# RAMPSXB.net
KiCad netlist of a schematic drawn in EAGLE
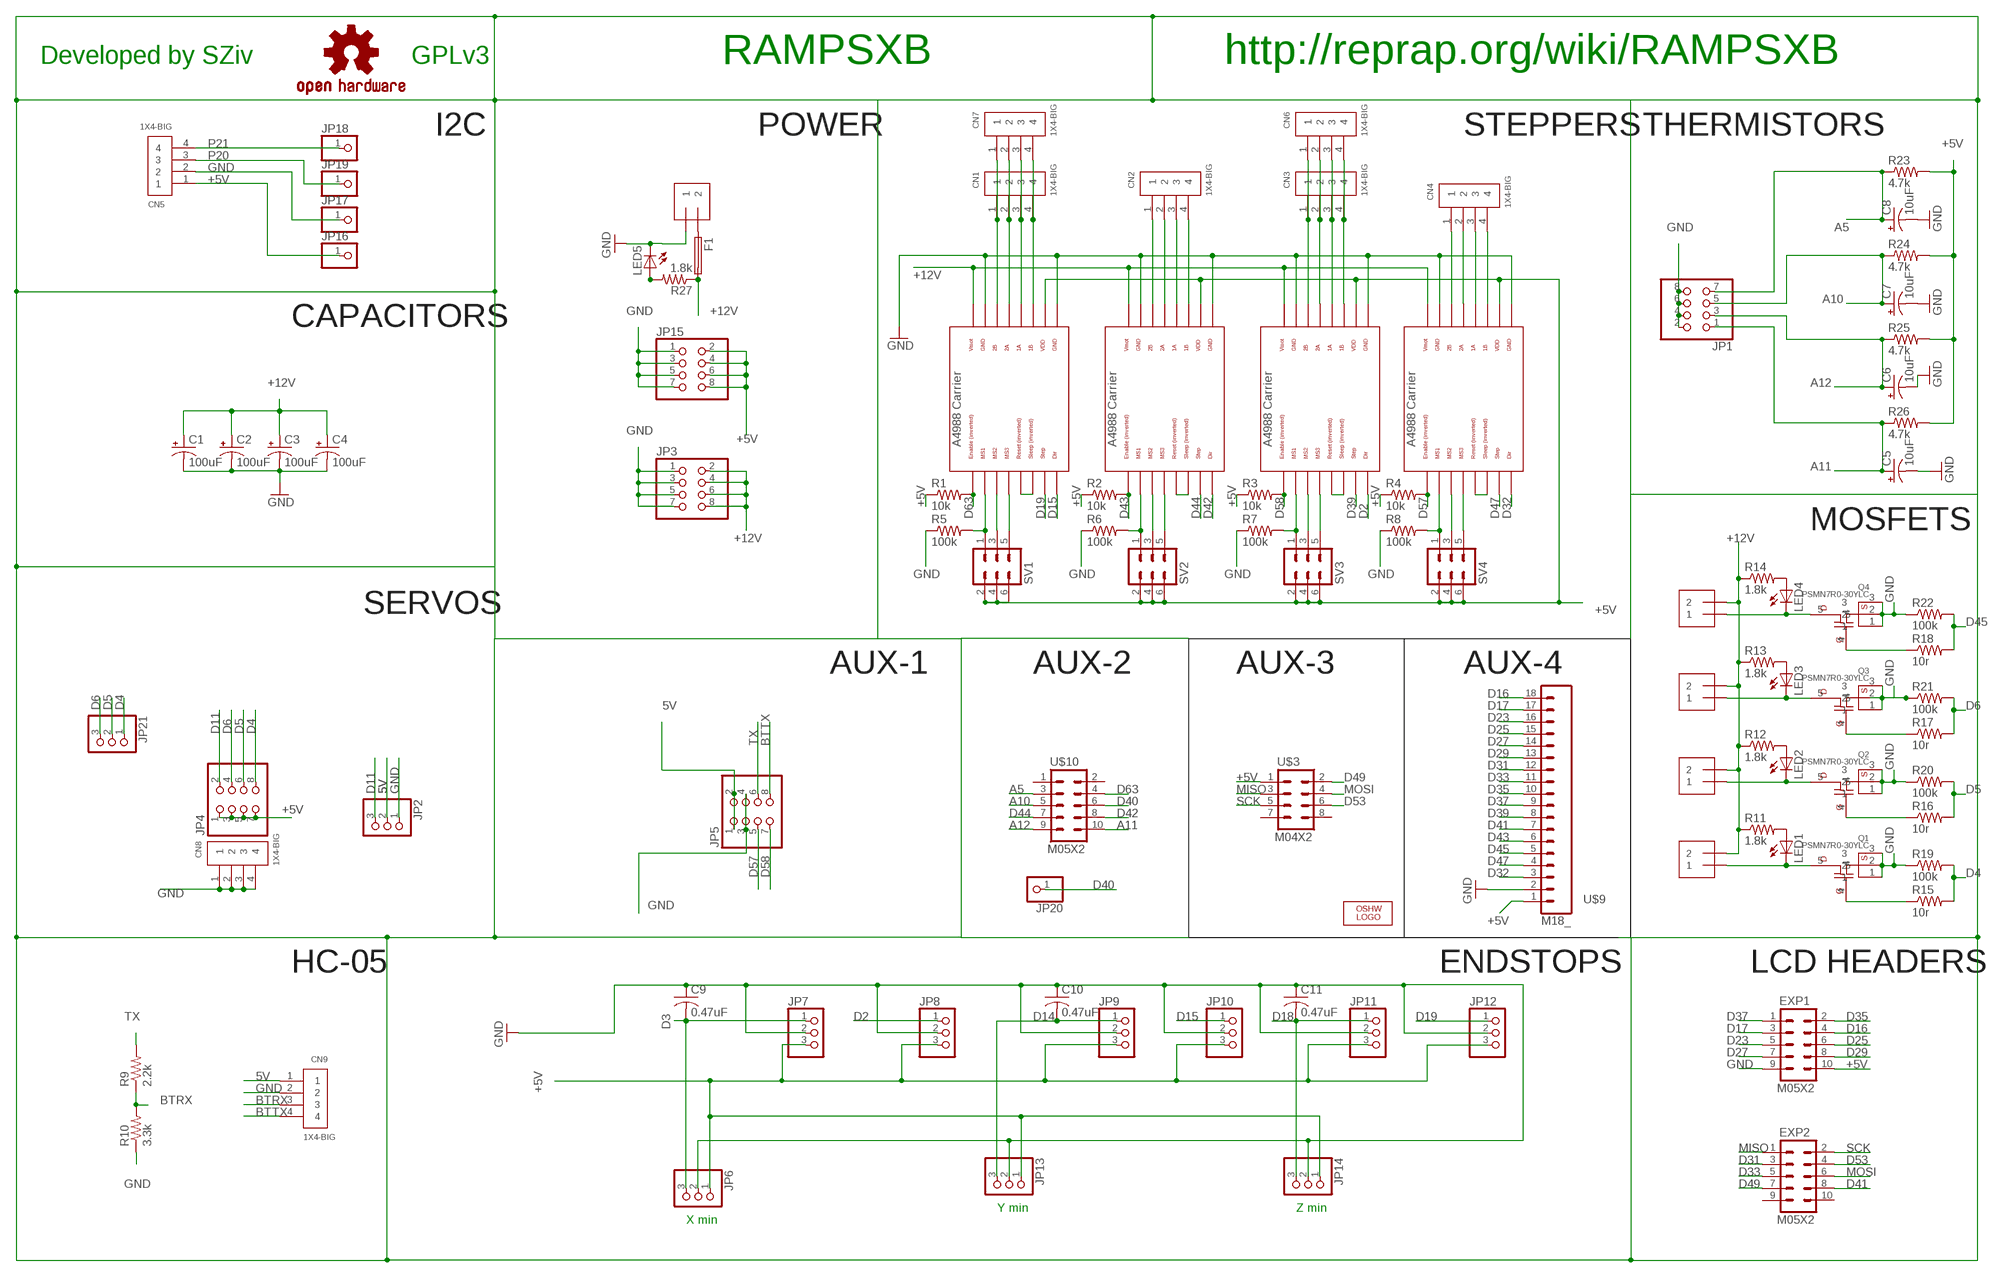
[diagram p0: schematic, sheet 1]

(export (version "E")
  (design (tool "Eeschema 10.0.6"))
  (components
    (comp (ref "C1")
      (value "100uF")
      (footprint "eagle-import:153CLV-0605")
      (libsource (lib "eagle-import") (part "CPOL-US153CLV-0605"))
    )
    (comp (ref "C2")
      (value "100uF")
      (footprint "eagle-import:153CLV-0605")
      (libsource (lib "eagle-import") (part "CPOL-US153CLV-0605"))
    )
    (comp (ref "C3")
      (value "100uF")
      (footprint "eagle-import:153CLV-0605")
      (libsource (lib "eagle-import") (part "CPOL-US153CLV-0605"))
    )
    (comp (ref "C4")
      (value "100uF")
      (footprint "eagle-import:153CLV-0605")
      (libsource (lib "eagle-import") (part "CPOL-US153CLV-0605"))
    )
    (comp (ref "C5")
      (value "10uF")
      (footprint "eagle-import:153CLV-0405")
      (libsource (lib "eagle-import") (part "CPOL-US153CLV-0405"))
    )
    (comp (ref "C6")
      (value "10uF")
      (footprint "eagle-import:153CLV-0405")
      (libsource (lib "eagle-import") (part "CPOL-US153CLV-0405"))
    )
    (comp (ref "C7")
      (value "10uF")
      (footprint "eagle-import:153CLV-0405")
      (libsource (lib "eagle-import") (part "CPOL-US153CLV-0405"))
    )
    (comp (ref "C8")
      (value "10uF")
      (footprint "eagle-import:153CLV-0405")
      (libsource (lib "eagle-import") (part "CPOL-US153CLV-0405"))
    )
    (comp (ref "C9")
      (value "0.47uF")
      (footprint "eagle-import:C0805")
      (libsource (lib "eagle-import") (part "C-USC0805"))
    )
    (comp (ref "C10")
      (value "0.47uF")
      (footprint "eagle-import:C0805")
      (libsource (lib "eagle-import") (part "C-USC0805"))
    )
    (comp (ref "C11")
      (value "0.47uF")
      (footprint "eagle-import:C0805")
      (libsource (lib "eagle-import") (part "C-USC0805"))
    )
    (comp (ref "CN1")
      (value "1X4-BIG")
      (footprint "eagle-import:1X04-BIG")
      (libsource (lib "eagle-import") (part "1X4-BIG"))
    )
    (comp (ref "CN2")
      (value "1X4-BIG")
      (footprint "eagle-import:1X04-BIG")
      (libsource (lib "eagle-import") (part "1X4-BIG"))
    )
    (comp (ref "CN3")
      (value "1X4-BIG")
      (footprint "eagle-import:1X04-BIG")
      (libsource (lib "eagle-import") (part "1X4-BIG"))
    )
    (comp (ref "CN4")
      (value "1X4-BIG")
      (footprint "eagle-import:1X04-BIG")
      (libsource (lib "eagle-import") (part "1X4-BIG"))
    )
    (comp (ref "CN5")
      (value "1X4-BIG")
      (footprint "eagle-import:1X04-BIG")
      (libsource (lib "eagle-import") (part "1X4-BIG"))
    )
    (comp (ref "CN6")
      (value "1X4-BIG")
      (footprint "eagle-import:1X04-BIG")
      (libsource (lib "eagle-import") (part "1X4-BIG"))
    )
    (comp (ref "CN7")
      (value "1X4-BIG")
      (footprint "eagle-import:1X04-BIG")
      (libsource (lib "eagle-import") (part "1X4-BIG"))
    )
    (comp (ref "CN8")
      (value "1X4-BIG")
      (footprint "eagle-import:1X04-BIG")
      (libsource (lib "eagle-import") (part "1X4-BIG"))
    )
    (comp (ref "CN9")
      (value "1X4-BIG")
      (footprint "eagle-import:1X04-BIG")
      (libsource (lib "eagle-import") (part "1X4-BIG"))
    )
    (comp (ref "EXP1")
      (value "M05X2")
      (footprint "eagle-import:2X5")
      (libsource (lib "eagle-import") (part "M05X2"))
    )
    (comp (ref "EXP2")
      (value "M05X2")
      (footprint "eagle-import:2X5")
      (libsource (lib "eagle-import") (part "M05X2"))
    )
    (comp (ref "F1")
      (value "PTCFUSE")
      (footprint "eagle-import:LITTLEFUSE")
      (libsource (lib "eagle-import") (part "PTCFUSE"))
    )
    (comp (ref "J1")
      (value "1X2-3.5MM")
      (footprint "eagle-import:1X2-3.5MM")
      (libsource (lib "eagle-import") (part "1X2-3.5MM"))
    )
    (comp (ref "J2")
      (value "1X2-3.5MM")
      (footprint "eagle-import:1X2-3.5MM")
      (libsource (lib "eagle-import") (part "1X2-3.5MM"))
    )
    (comp (ref "J3")
      (value "1X2-3.5MM")
      (footprint "eagle-import:1X2-3.5MM")
      (libsource (lib "eagle-import") (part "1X2-3.5MM"))
    )
    (comp (ref "J4")
      (value "1X2-3.5MM")
      (footprint "eagle-import:1X2-3.5MM")
      (libsource (lib "eagle-import") (part "1X2-3.5MM"))
    )
    (comp (ref "J5")
      (value "1X2-3.5MM")
      (footprint "eagle-import:1X2-3.5MM")
      (libsource (lib "eagle-import") (part "1X2-3.5MM"))
    )
    (comp (ref "JP1")
      (value "PINHD-2X4")
      (footprint "eagle-import:2X04")
      (libsource (lib "eagle-import") (part "PINHD-2X4"))
    )
    (comp (ref "JP2")
      (value "PINHD-1X3")
      (footprint "eagle-import:1X03")
      (libsource (lib "eagle-import") (part "PINHD-1X3"))
    )
    (comp (ref "JP3")
      (value "PINHD-2X4")
      (footprint "eagle-import:2X04")
      (libsource (lib "eagle-import") (part "PINHD-2X4"))
    )
    (comp (ref "JP4")
      (value "PINHD-2X4")
      (footprint "eagle-import:2X04")
      (libsource (lib "eagle-import") (part "PINHD-2X4"))
    )
    (comp (ref "JP5")
      (value "PINHD-2X4")
      (footprint "eagle-import:2X04")
      (libsource (lib "eagle-import") (part "PINHD-2X4"))
    )
    (comp (ref "JP6")
      (value "PINHD-1X3")
      (footprint "eagle-import:1X03")
      (libsource (lib "eagle-import") (part "PINHD-1X3"))
    )
    (comp (ref "JP7")
      (value "PINHD-1X3")
      (footprint "eagle-import:1X03")
      (libsource (lib "eagle-import") (part "PINHD-1X3"))
    )
    (comp (ref "JP8")
      (value "PINHD-1X3")
      (footprint "eagle-import:1X03")
      (libsource (lib "eagle-import") (part "PINHD-1X3"))
    )
    (comp (ref "JP9")
      (value "PINHD-1X3")
      (footprint "eagle-import:1X03")
      (libsource (lib "eagle-import") (part "PINHD-1X3"))
    )
    (comp (ref "JP10")
      (value "PINHD-1X3")
      (footprint "eagle-import:1X03")
      (libsource (lib "eagle-import") (part "PINHD-1X3"))
    )
    (comp (ref "JP11")
      (value "PINHD-1X3")
      (footprint "eagle-import:1X03")
      (libsource (lib "eagle-import") (part "PINHD-1X3"))
    )
    (comp (ref "JP12")
      (value "PINHD-1X3")
      (footprint "eagle-import:1X03")
      (libsource (lib "eagle-import") (part "PINHD-1X3"))
    )
    (comp (ref "JP13")
      (value "PINHD-1X3")
      (footprint "eagle-import:1X03")
      (libsource (lib "eagle-import") (part "PINHD-1X3"))
    )
    (comp (ref "JP14")
      (value "PINHD-1X3")
      (footprint "eagle-import:1X03")
      (libsource (lib "eagle-import") (part "PINHD-1X3"))
    )
    (comp (ref "JP15")
      (value "PINHD-2X4")
      (footprint "eagle-import:2X04")
      (libsource (lib "eagle-import") (part "PINHD-2X4"))
    )
    (comp (ref "JP16")
      (value "PINHD-1X1")
      (footprint "eagle-import:1X01")
      (libsource (lib "eagle-import") (part "PINHD-1X1"))
    )
    (comp (ref "JP17")
      (value "PINHD-1X1")
      (footprint "eagle-import:1X01")
      (libsource (lib "eagle-import") (part "PINHD-1X1"))
    )
    (comp (ref "JP18")
      (value "PINHD-1X1")
      (footprint "eagle-import:1X01")
      (libsource (lib "eagle-import") (part "PINHD-1X1"))
    )
    (comp (ref "JP19")
      (value "PINHD-1X1")
      (footprint "eagle-import:1X01")
      (libsource (lib "eagle-import") (part "PINHD-1X1"))
    )
    (comp (ref "JP20")
      (value "PINHD-1X1")
      (footprint "eagle-import:1X01")
      (libsource (lib "eagle-import") (part "PINHD-1X1"))
    )
    (comp (ref "JP21")
      (value "PINHD-1X3")
      (footprint "eagle-import:1X03")
      (libsource (lib "eagle-import") (part "PINHD-1X3"))
    )
    (comp (ref "LED1")
      (value "LEDCHIPLED_0805")
      (footprint "eagle-import:CHIPLED_0805")
      (libsource (lib "eagle-import") (part "LEDCHIPLED_0805"))
    )
    (comp (ref "LED2")
      (value "LEDCHIPLED_0805")
      (footprint "eagle-import:CHIPLED_0805")
      (libsource (lib "eagle-import") (part "LEDCHIPLED_0805"))
    )
    (comp (ref "LED3")
      (value "LEDCHIPLED_0805")
      (footprint "eagle-import:CHIPLED_0805")
      (libsource (lib "eagle-import") (part "LEDCHIPLED_0805"))
    )
    (comp (ref "LED4")
      (value "LEDCHIPLED_0805")
      (footprint "eagle-import:CHIPLED_0805")
      (libsource (lib "eagle-import") (part "LEDCHIPLED_0805"))
    )
    (comp (ref "LED5")
      (value "LEDCHIPLED_0805")
      (footprint "eagle-import:CHIPLED_0805")
      (libsource (lib "eagle-import") (part "LEDCHIPLED_0805"))
    )
    (comp (ref "LOGO1")
      (value "OSHW_LOGO_6MILX0100-NT")
      (footprint "eagle-import:OSHW_6X100_NOTEXT")
      (libsource (lib "eagle-import") (part "OSHW_LOGO_6MILX0100-NT"))
    )
    (comp (ref "LOGO2")
      (value "OSHW-LOGOL")
      (footprint "eagle-import:OSHW-LOGO-L")
      (libsource (lib "eagle-import") (part "OSHW-LOGOL"))
    )
    (comp (ref "Q1")
      (value "PSMN7R0-30YLC")
      (footprint "eagle-import:LFPAK")
      (libsource (lib "eagle-import") (part "PSMN7R0-30YLC"))
    )
    (comp (ref "Q2")
      (value "PSMN7R0-30YLC")
      (footprint "eagle-import:LFPAK")
      (libsource (lib "eagle-import") (part "PSMN7R0-30YLC"))
    )
    (comp (ref "Q3")
      (value "PSMN7R0-30YLC")
      (footprint "eagle-import:LFPAK")
      (libsource (lib "eagle-import") (part "PSMN7R0-30YLC"))
    )
    (comp (ref "Q4")
      (value "PSMN7R0-30YLC")
      (footprint "eagle-import:LFPAK")
      (libsource (lib "eagle-import") (part "PSMN7R0-30YLC"))
    )
    (comp (ref "R1")
      (value "10k")
      (footprint "eagle-import:M0805")
      (libsource (lib "eagle-import") (part "R-US_M0805"))
    )
    (comp (ref "R2")
      (value "10k")
      (footprint "eagle-import:M0805")
      (libsource (lib "eagle-import") (part "R-US_M0805"))
    )
    (comp (ref "R3")
      (value "10k")
      (footprint "eagle-import:M0805")
      (libsource (lib "eagle-import") (part "R-US_M0805"))
    )
    (comp (ref "R4")
      (value "10k")
      (footprint "eagle-import:M0805")
      (libsource (lib "eagle-import") (part "R-US_M0805"))
    )
    (comp (ref "R5")
      (value "100k")
      (footprint "eagle-import:M0805")
      (libsource (lib "eagle-import") (part "R-US_M0805"))
    )
    (comp (ref "R6")
      (value "100k")
      (footprint "eagle-import:M0805")
      (libsource (lib "eagle-import") (part "R-US_M0805"))
    )
    (comp (ref "R7")
      (value "100k")
      (footprint "eagle-import:M0805")
      (libsource (lib "eagle-import") (part "R-US_M0805"))
    )
    (comp (ref "R8")
      (value "100k")
      (footprint "eagle-import:M0805")
      (libsource (lib "eagle-import") (part "R-US_M0805"))
    )
    (comp (ref "R9")
      (value "2.2k")
      (footprint "eagle-import:M0805")
      (libsource (lib "eagle-import") (part "R-US_M0805"))
    )
    (comp (ref "R10")
      (value "3.3k")
      (footprint "eagle-import:M0805")
      (libsource (lib "eagle-import") (part "R-US_M0805"))
    )
    (comp (ref "R11")
      (value "1.8k")
      (footprint "eagle-import:M0805")
      (libsource (lib "eagle-import") (part "R-US_M0805"))
    )
    (comp (ref "R12")
      (value "1.8k")
      (footprint "eagle-import:M0805")
      (libsource (lib "eagle-import") (part "R-US_M0805"))
    )
    (comp (ref "R13")
      (value "1.8k")
      (footprint "eagle-import:M0805")
      (libsource (lib "eagle-import") (part "R-US_M0805"))
    )
    (comp (ref "R14")
      (value "1.8k")
      (footprint "eagle-import:M0805")
      (libsource (lib "eagle-import") (part "R-US_M0805"))
    )
    (comp (ref "R15")
      (value "10r")
      (footprint "eagle-import:M0805")
      (libsource (lib "eagle-import") (part "R-US_M0805"))
    )
    (comp (ref "R16")
      (value "10r")
      (footprint "eagle-import:M0805")
      (libsource (lib "eagle-import") (part "R-US_M0805"))
    )
    (comp (ref "R17")
      (value "10r")
      (footprint "eagle-import:M0805")
      (libsource (lib "eagle-import") (part "R-US_M0805"))
    )
    (comp (ref "R18")
      (value "10r")
      (footprint "eagle-import:M0805")
      (libsource (lib "eagle-import") (part "R-US_M0805"))
    )
    (comp (ref "R19")
      (value "100k")
      (footprint "eagle-import:M0805")
      (libsource (lib "eagle-import") (part "R-US_M0805"))
    )
    (comp (ref "R20")
      (value "100k")
      (footprint "eagle-import:M0805")
      (libsource (lib "eagle-import") (part "R-US_M0805"))
    )
    (comp (ref "R21")
      (value "100k")
      (footprint "eagle-import:M0805")
      (libsource (lib "eagle-import") (part "R-US_M0805"))
    )
    (comp (ref "R22")
      (value "100k")
      (footprint "eagle-import:M0805")
      (libsource (lib "eagle-import") (part "R-US_M0805"))
    )
    (comp (ref "R23")
      (value "4.7k")
      (footprint "eagle-import:R0805")
      (libsource (lib "eagle-import") (part "R-US_R0805"))
    )
    (comp (ref "R24")
      (value "4.7k")
      (footprint "eagle-import:R0805")
      (libsource (lib "eagle-import") (part "R-US_R0805"))
    )
    (comp (ref "R25")
      (value "4.7k")
      (footprint "eagle-import:R0805")
      (libsource (lib "eagle-import") (part "R-US_R0805"))
    )
    (comp (ref "R26")
      (value "4.7k")
      (footprint "eagle-import:R0805")
      (libsource (lib "eagle-import") (part "R-US_R0805"))
    )
    (comp (ref "R27")
      (value "1.8k")
      (footprint "eagle-import:M0805")
      (libsource (lib "eagle-import") (part "R-US_M0805"))
    )
    (comp (ref "SV1")
      (value "MA03-2")
      (footprint "eagle-import:MA03-2")
      (libsource (lib "eagle-import") (part "MA03-2"))
    )
    (comp (ref "SV2")
      (value "MA03-2")
      (footprint "eagle-import:MA03-2")
      (libsource (lib "eagle-import") (part "MA03-2"))
    )
    (comp (ref "SV3")
      (value "MA03-2")
      (footprint "eagle-import:MA03-2")
      (libsource (lib "eagle-import") (part "MA03-2"))
    )
    (comp (ref "SV4")
      (value "MA03-2")
      (footprint "eagle-import:MA03-2")
      (libsource (lib "eagle-import") (part "MA03-2"))
    )
    (comp (ref "U$1")
      (value "POLOLU_A4983CARRIER")
      (footprint "eagle-import:A4988BREAKOUT")
      (libsource (lib "eagle-import") (part "POLOLU_A4983CARRIER"))
    )
    (comp (ref "U$2")
      (value "POLOLU_A4983CARRIER")
      (footprint "eagle-import:A4988BREAKOUT")
      (libsource (lib "eagle-import") (part "POLOLU_A4983CARRIER"))
    )
    (comp (ref "U$3")
      (value "M04X2")
      (footprint "eagle-import:2X4")
      (libsource (lib "eagle-import") (part "M04X2"))
    )
    (comp (ref "U$4")
      (value "POLOLU_A4983CARRIER")
      (footprint "eagle-import:A4988BREAKOUT")
      (libsource (lib "eagle-import") (part "POLOLU_A4983CARRIER"))
    )
    (comp (ref "U$5")
      (value "POLOLU_A4983CARRIER")
      (footprint "eagle-import:A4988BREAKOUT")
      (libsource (lib "eagle-import") (part "POLOLU_A4983CARRIER"))
    )
    (comp (ref "U$9")
      (value "M18_")
      (footprint "eagle-import:1X18")
      (libsource (lib "eagle-import") (part "M18_"))
    )
    (comp (ref "U$10")
      (value "M05X2")
      (footprint "eagle-import:2X5")
      (libsource (lib "eagle-import") (part "M05X2"))
    )
  )
  (nets
    (net (code "1") (name "/+5V") (class "Default")
      (node (ref "CN5") (pin "1") (pinfunction "1_1") (pintype "bidirectional"))
      (node (ref "EXP1") (pin "10") (pinfunction "10_10") (pintype "passive"))
      (node (ref "JP10") (pin "3") (pinfunction "3_3") (pintype "passive"))
      (node (ref "JP11") (pin "3") (pinfunction "3_3") (pintype "passive"))
      (node (ref "JP12") (pin "3") (pinfunction "3_3") (pintype "passive"))
      (node (ref "JP13") (pin "1") (pinfunction "1_1") (pintype "passive"))
      (node (ref "JP14") (pin "1") (pinfunction "1_1") (pintype "passive"))
      (node (ref "JP15") (pin "2") (pinfunction "2_2") (pintype "passive"))
      (node (ref "JP15") (pin "4") (pinfunction "4_4") (pintype "passive"))
      (node (ref "JP15") (pin "6") (pinfunction "6_6") (pintype "passive"))
      (node (ref "JP15") (pin "8") (pinfunction "8_8") (pintype "passive"))
      (node (ref "JP16") (pin "1") (pinfunction "1_1") (pintype "passive"))
      (node (ref "JP4") (pin "1") (pinfunction "1_1") (pintype "passive"))
      (node (ref "JP4") (pin "3") (pinfunction "3_3") (pintype "passive"))
      (node (ref "JP4") (pin "5") (pinfunction "5_5") (pintype "passive"))
      (node (ref "JP4") (pin "7") (pinfunction "7_7") (pintype "passive"))
      (node (ref "JP6") (pin "1") (pinfunction "1_1") (pintype "passive"))
      (node (ref "JP7") (pin "3") (pinfunction "3_3") (pintype "passive"))
      (node (ref "JP8") (pin "3") (pinfunction "3_3") (pintype "passive"))
      (node (ref "JP9") (pin "3") (pinfunction "3_3") (pintype "passive"))
      (node (ref "R1") (pin "1") (pinfunction "1_1") (pintype "passive"))
      (node (ref "R2") (pin "1") (pinfunction "1_1") (pintype "passive"))
      (node (ref "R23") (pin "2") (pinfunction "2_2") (pintype "passive"))
      (node (ref "R24") (pin "2") (pinfunction "2_2") (pintype "passive"))
      (node (ref "R25") (pin "2") (pinfunction "2_2") (pintype "passive"))
      (node (ref "R26") (pin "2") (pinfunction "2_2") (pintype "passive"))
      (node (ref "R3") (pin "1") (pinfunction "1_1") (pintype "passive"))
      (node (ref "R4") (pin "1") (pinfunction "1_1") (pintype "passive"))
      (node (ref "SV1") (pin "2") (pinfunction "2_2") (pintype "passive"))
      (node (ref "SV1") (pin "4") (pinfunction "4_4") (pintype "passive"))
      (node (ref "SV1") (pin "6") (pinfunction "6_6") (pintype "passive"))
      (node (ref "SV2") (pin "2") (pinfunction "2_2") (pintype "passive"))
      (node (ref "SV2") (pin "4") (pinfunction "4_4") (pintype "passive"))
      (node (ref "SV2") (pin "6") (pinfunction "6_6") (pintype "passive"))
      (node (ref "SV3") (pin "2") (pinfunction "2_2") (pintype "passive"))
      (node (ref "SV3") (pin "4") (pinfunction "4_4") (pintype "passive"))
      (node (ref "SV3") (pin "6") (pinfunction "6_6") (pintype "passive"))
      (node (ref "SV4") (pin "2") (pinfunction "2_2") (pintype "passive"))
      (node (ref "SV4") (pin "4") (pinfunction "4_4") (pintype "passive"))
      (node (ref "SV4") (pin "6") (pinfunction "6_6") (pintype "passive"))
      (node (ref "U$1") (pin "VDD") (pinfunction "VDD_VDD") (pintype "power_in"))
      (node (ref "U$2") (pin "VDD") (pinfunction "VDD_VDD") (pintype "power_in"))
      (node (ref "U$3") (pin "1") (pinfunction "1_1") (pintype "passive"))
      (node (ref "U$4") (pin "VDD") (pinfunction "VDD_VDD") (pintype "power_in"))
      (node (ref "U$5") (pin "VDD") (pinfunction "VDD_VDD") (pintype "power_in"))
      (node (ref "U$9") (pin "1") (pinfunction "1_1") (pintype "passive"))
    )
    (net (code "2") (name "/+12V") (class "Default")
      (node (ref "C1") (pin "+") (pinfunction "+_+") (pintype "passive"))
      (node (ref "C2") (pin "+") (pinfunction "+_+") (pintype "passive"))
      (node (ref "C3") (pin "+") (pinfunction "+_+") (pintype "passive"))
      (node (ref "C4") (pin "+") (pinfunction "+_+") (pintype "passive"))
      (node (ref "F1") (pin "2") (pinfunction "2_2") (pintype "passive"))
      (node (ref "J2") (pin "2") (pinfunction "2_2") (pintype "passive"))
      (node (ref "J3") (pin "2") (pinfunction "2_2") (pintype "passive"))
      (node (ref "J4") (pin "2") (pinfunction "2_2") (pintype "passive"))
      (node (ref "J5") (pin "2") (pinfunction "2_2") (pintype "passive"))
      (node (ref "JP3") (pin "2") (pinfunction "2_2") (pintype "passive"))
      (node (ref "JP3") (pin "4") (pinfunction "4_4") (pintype "passive"))
      (node (ref "JP3") (pin "6") (pinfunction "6_6") (pintype "passive"))
      (node (ref "JP3") (pin "8") (pinfunction "8_8") (pintype "passive"))
      (node (ref "R11") (pin "1") (pinfunction "1_1") (pintype "passive"))
      (node (ref "R12") (pin "1") (pinfunction "1_1") (pintype "passive"))
      (node (ref "R13") (pin "1") (pinfunction "1_1") (pintype "passive"))
      (node (ref "R14") (pin "1") (pinfunction "1_1") (pintype "passive"))
      (node (ref "R27") (pin "1") (pinfunction "1_1") (pintype "passive"))
      (node (ref "U$1") (pin "VMOT") (pinfunction "VMOT_VMOT") (pintype "power_in"))
      (node (ref "U$2") (pin "VMOT") (pinfunction "VMOT_VMOT") (pintype "power_in"))
      (node (ref "U$4") (pin "VMOT") (pinfunction "VMOT_VMOT") (pintype "power_in"))
      (node (ref "U$5") (pin "VMOT") (pinfunction "VMOT_VMOT") (pintype "power_in"))
    )
    (net (code "3") (name "/5V") (class "Default")
      (node (ref "CN9") (pin "1") (pinfunction "1_1") (pintype "bidirectional"))
      (node (ref "JP2") (pin "2") (pinfunction "2_2") (pintype "passive"))
      (node (ref "JP5") (pin "1") (pinfunction "1_1") (pintype "passive"))
      (node (ref "JP5") (pin "2") (pinfunction "2_2") (pintype "passive"))
    )
    (net (code "4") (name "/A5") (class "Default")
      (node (ref "C8") (pin "+") (pinfunction "+_+") (pintype "passive"))
      (node (ref "JP1") (pin "7") (pinfunction "7_7") (pintype "passive"))
      (node (ref "R23") (pin "1") (pinfunction "1_1") (pintype "passive"))
      (node (ref "U$10") (pin "3") (pinfunction "3_3") (pintype "passive"))
    )
    (net (code "5") (name "/A10") (class "Default")
      (node (ref "C7") (pin "+") (pinfunction "+_+") (pintype "passive"))
      (node (ref "JP1") (pin "5") (pinfunction "5_5") (pintype "passive"))
      (node (ref "R24") (pin "1") (pinfunction "1_1") (pintype "passive"))
      (node (ref "U$10") (pin "5") (pinfunction "5_5") (pintype "passive"))
    )
    (net (code "6") (name "/A11") (class "Default")
      (node (ref "C5") (pin "+") (pinfunction "+_+") (pintype "passive"))
      (node (ref "JP1") (pin "1") (pinfunction "1_1") (pintype "passive"))
      (node (ref "R26") (pin "1") (pinfunction "1_1") (pintype "passive"))
      (node (ref "U$10") (pin "10") (pinfunction "10_10") (pintype "passive"))
    )
    (net (code "7") (name "/A12") (class "Default")
      (node (ref "C6") (pin "+") (pinfunction "+_+") (pintype "passive"))
      (node (ref "JP1") (pin "3") (pinfunction "3_3") (pintype "passive"))
      (node (ref "R25") (pin "1") (pinfunction "1_1") (pintype "passive"))
      (node (ref "U$10") (pin "9") (pinfunction "9_9") (pintype "passive"))
    )
    (net (code "8") (name "/BTRX") (class "Default")
      (node (ref "CN9") (pin "3") (pinfunction "3_3") (pintype "bidirectional"))
      (node (ref "R10") (pin "2") (pinfunction "2_2") (pintype "passive"))
      (node (ref "R9") (pin "1") (pinfunction "1_1") (pintype "passive"))
    )
    (net (code "9") (name "/BTTX") (class "Default")
      (node (ref "CN9") (pin "4") (pinfunction "4_4") (pintype "bidirectional"))
      (node (ref "JP5") (pin "8") (pinfunction "8_8") (pintype "passive"))
    )
    (net (code "10") (name "/D2") (class "Default")
      (node (ref "JP8") (pin "1") (pinfunction "1_1") (pintype "passive"))
      (node (ref "U$4") (pin "DIR") (pinfunction "DIR_DIR") (pintype "input"))
    )
    (net (code "11") (name "/D3") (class "Default")
      (node (ref "C9") (pin "2") (pinfunction "2_2") (pintype "passive"))
      (node (ref "JP6") (pin "3") (pinfunction "3_3") (pintype "passive"))
      (node (ref "JP7") (pin "1") (pinfunction "1_1") (pintype "passive"))
    )
    (net (code "12") (name "/D4") (class "Default")
      (node (ref "JP21") (pin "1") (pinfunction "1_1") (pintype "passive"))
      (node (ref "JP4") (pin "8") (pinfunction "8_8") (pintype "passive"))
      (node (ref "R15") (pin "2") (pinfunction "2_2") (pintype "passive"))
      (node (ref "R19") (pin "2") (pinfunction "2_2") (pintype "passive"))
    )
    (net (code "13") (name "/D5") (class "Default")
      (node (ref "JP21") (pin "2") (pinfunction "2_2") (pintype "passive"))
      (node (ref "JP4") (pin "6") (pinfunction "6_6") (pintype "passive"))
      (node (ref "R16") (pin "2") (pinfunction "2_2") (pintype "passive"))
      (node (ref "R20") (pin "2") (pinfunction "2_2") (pintype "passive"))
    )
    (net (code "14") (name "/D6") (class "Default")
      (node (ref "JP21") (pin "3") (pinfunction "3_3") (pintype "passive"))
      (node (ref "JP4") (pin "4") (pinfunction "4_4") (pintype "passive"))
      (node (ref "R17") (pin "2") (pinfunction "2_2") (pintype "passive"))
      (node (ref "R21") (pin "2") (pinfunction "2_2") (pintype "passive"))
    )
    (net (code "15") (name "/D11") (class "Default")
      (node (ref "JP2") (pin "3") (pinfunction "3_3") (pintype "passive"))
      (node (ref "JP4") (pin "2") (pinfunction "2_2") (pintype "passive"))
    )
    (net (code "16") (name "/D14") (class "Default")
      (node (ref "C10") (pin "2") (pinfunction "2_2") (pintype "passive"))
      (node (ref "JP13") (pin "3") (pinfunction "3_3") (pintype "passive"))
      (node (ref "JP9") (pin "1") (pinfunction "1_1") (pintype "passive"))
    )
    (net (code "17") (name "/D15") (class "Default")
      (node (ref "JP10") (pin "1") (pinfunction "1_1") (pintype "passive"))
      (node (ref "U$1") (pin "DIR") (pinfunction "DIR_DIR") (pintype "input"))
    )
    (net (code "18") (name "/D16") (class "Default")
      (node (ref "EXP1") (pin "4") (pinfunction "4_4") (pintype "passive"))
      (node (ref "U$9") (pin "18") (pinfunction "18_18") (pintype "passive"))
    )
    (net (code "19") (name "/D17") (class "Default")
      (node (ref "EXP1") (pin "3") (pinfunction "3_3") (pintype "passive"))
      (node (ref "U$9") (pin "17") (pinfunction "17_17") (pintype "passive"))
    )
    (net (code "20") (name "/D18") (class "Default")
      (node (ref "C11") (pin "2") (pinfunction "2_2") (pintype "passive"))
      (node (ref "JP11") (pin "1") (pinfunction "1_1") (pintype "passive"))
      (node (ref "JP14") (pin "3") (pinfunction "3_3") (pintype "passive"))
    )
    (net (code "21") (name "/D19") (class "Default")
      (node (ref "JP12") (pin "1") (pinfunction "1_1") (pintype "passive"))
      (node (ref "U$1") (pin "STEP") (pinfunction "STEP_STEP") (pintype "input"))
    )
    (net (code "22") (name "/D23") (class "Default")
      (node (ref "EXP1") (pin "5") (pinfunction "5_5") (pintype "passive"))
      (node (ref "U$9") (pin "16") (pinfunction "16_16") (pintype "passive"))
    )
    (net (code "23") (name "/D25") (class "Default")
      (node (ref "EXP1") (pin "6") (pinfunction "6_6") (pintype "passive"))
      (node (ref "U$9") (pin "15") (pinfunction "15_15") (pintype "passive"))
    )
    (net (code "24") (name "/D27") (class "Default")
      (node (ref "EXP1") (pin "7") (pinfunction "7_7") (pintype "passive"))
      (node (ref "U$9") (pin "14") (pinfunction "14_14") (pintype "passive"))
    )
    (net (code "25") (name "/D29") (class "Default")
      (node (ref "EXP1") (pin "8") (pinfunction "8_8") (pintype "passive"))
      (node (ref "U$9") (pin "13") (pinfunction "13_13") (pintype "passive"))
    )
    (net (code "26") (name "/D31") (class "Default")
      (node (ref "EXP2") (pin "3") (pinfunction "3_3") (pintype "passive"))
      (node (ref "U$9") (pin "12") (pinfunction "12_12") (pintype "passive"))
    )
    (net (code "27") (name "/D32") (class "Default")
      (node (ref "U$5") (pin "DIR") (pinfunction "DIR_DIR") (pintype "input"))
      (node (ref "U$9") (pin "3") (pinfunction "3_3") (pintype "passive"))
    )
    (net (code "28") (name "/D33") (class "Default")
      (node (ref "EXP2") (pin "5") (pinfunction "5_5") (pintype "passive"))
      (node (ref "U$9") (pin "11") (pinfunction "11_11") (pintype "passive"))
    )
    (net (code "29") (name "/D35") (class "Default")
      (node (ref "EXP1") (pin "2") (pinfunction "2_2") (pintype "passive"))
      (node (ref "U$9") (pin "10") (pinfunction "10_10") (pintype "passive"))
    )
    (net (code "30") (name "/D37") (class "Default")
      (node (ref "EXP1") (pin "1") (pinfunction "1_1") (pintype "passive"))
      (node (ref "U$9") (pin "9") (pinfunction "9_9") (pintype "passive"))
    )
    (net (code "31") (name "/D39") (class "Default")
      (node (ref "U$4") (pin "STEP") (pinfunction "STEP_STEP") (pintype "input"))
      (node (ref "U$9") (pin "8") (pinfunction "8_8") (pintype "passive"))
    )
    (net (code "32") (name "/D40") (class "Default")
      (node (ref "JP20") (pin "1") (pinfunction "1_1") (pintype "passive"))
      (node (ref "U$10") (pin "6") (pinfunction "6_6") (pintype "passive"))
    )
    (net (code "33") (name "/D41") (class "Default")
      (node (ref "EXP2") (pin "8") (pinfunction "8_8") (pintype "passive"))
      (node (ref "U$9") (pin "7") (pinfunction "7_7") (pintype "passive"))
    )
    (net (code "34") (name "/D42") (class "Default")
      (node (ref "U$10") (pin "8") (pinfunction "8_8") (pintype "passive"))
      (node (ref "U$2") (pin "DIR") (pinfunction "DIR_DIR") (pintype "input"))
    )
    (net (code "35") (name "/D43") (class "Default")
      (node (ref "R2") (pin "2") (pinfunction "2_2") (pintype "passive"))
      (node (ref "U$2") (pin "EN") (pinfunction "EN_EN") (pintype "input"))
      (node (ref "U$9") (pin "6") (pinfunction "6_6") (pintype "passive"))
    )
    (net (code "36") (name "/D44") (class "Default")
      (node (ref "U$10") (pin "7") (pinfunction "7_7") (pintype "passive"))
      (node (ref "U$2") (pin "STEP") (pinfunction "STEP_STEP") (pintype "input"))
    )
    (net (code "37") (name "/D45") (class "Default")
      (node (ref "R18") (pin "2") (pinfunction "2_2") (pintype "passive"))
      (node (ref "R22") (pin "2") (pinfunction "2_2") (pintype "passive"))
      (node (ref "U$9") (pin "5") (pinfunction "5_5") (pintype "passive"))
    )
    (net (code "38") (name "/D47") (class "Default")
      (node (ref "U$5") (pin "STEP") (pinfunction "STEP_STEP") (pintype "input"))
      (node (ref "U$9") (pin "4") (pinfunction "4_4") (pintype "passive"))
    )
    (net (code "39") (name "/D49") (class "Default")
      (node (ref "EXP2") (pin "7") (pinfunction "7_7") (pintype "passive"))
      (node (ref "U$3") (pin "2") (pinfunction "2_2") (pintype "passive"))
    )
    (net (code "40") (name "/D53") (class "Default")
      (node (ref "EXP2") (pin "4") (pinfunction "4_4") (pintype "passive"))
      (node (ref "U$3") (pin "6") (pinfunction "6_6") (pintype "passive"))
    )
    (net (code "41") (name "/D57") (class "Default")
      (node (ref "JP5") (pin "5") (pinfunction "5_5") (pintype "passive"))
      (node (ref "R4") (pin "2") (pinfunction "2_2") (pintype "passive"))
      (node (ref "U$5") (pin "EN") (pinfunction "EN_EN") (pintype "input"))
    )
    (net (code "42") (name "/D58") (class "Default")
      (node (ref "JP5") (pin "7") (pinfunction "7_7") (pintype "passive"))
      (node (ref "R3") (pin "2") (pinfunction "2_2") (pintype "passive"))
      (node (ref "U$4") (pin "EN") (pinfunction "EN_EN") (pintype "input"))
    )
    (net (code "43") (name "/D63") (class "Default")
      (node (ref "R1") (pin "2") (pinfunction "2_2") (pintype "passive"))
      (node (ref "U$1") (pin "EN") (pinfunction "EN_EN") (pintype "input"))
      (node (ref "U$10") (pin "4") (pinfunction "4_4") (pintype "passive"))
    )
    (net (code "44") (name "/MISO") (class "Default")
      (node (ref "EXP2") (pin "1") (pinfunction "1_1") (pintype "passive"))
      (node (ref "U$3") (pin "3") (pinfunction "3_3") (pintype "passive"))
    )
    (net (code "45") (name "/MOSI") (class "Default")
      (node (ref "EXP2") (pin "6") (pinfunction "6_6") (pintype "passive"))
      (node (ref "U$3") (pin "4") (pinfunction "4_4") (pintype "passive"))
    )
    (net (code "46") (name "/P20") (class "Default")
      (node (ref "CN5") (pin "3") (pinfunction "3_3") (pintype "bidirectional"))
      (node (ref "JP19") (pin "1") (pinfunction "1_1") (pintype "passive"))
    )
    (net (code "47") (name "/P21") (class "Default")
      (node (ref "CN5") (pin "4") (pinfunction "4_4") (pintype "bidirectional"))
      (node (ref "JP18") (pin "1") (pinfunction "1_1") (pintype "passive"))
    )
    (net (code "48") (name "/SCK") (class "Default")
      (node (ref "EXP2") (pin "2") (pinfunction "2_2") (pintype "passive"))
      (node (ref "U$3") (pin "5") (pinfunction "5_5") (pintype "passive"))
    )
    (net (code "49") (name "/TX") (class "Default")
      (node (ref "JP5") (pin "6") (pinfunction "6_6") (pintype "passive"))
      (node (ref "R9") (pin "2") (pinfunction "2_2") (pintype "passive"))
    )
    (net (code "50") (name "GND") (class "Default")
      (node (ref "C1") (pin "-") (pinfunction "-_-") (pintype "passive"))
      (node (ref "C10") (pin "1") (pinfunction "1_1") (pintype "passive"))
      (node (ref "C11") (pin "1") (pinfunction "1_1") (pintype "passive"))
      (node (ref "C2") (pin "-") (pinfunction "-_-") (pintype "passive"))
      (node (ref "C3") (pin "-") (pinfunction "-_-") (pintype "passive"))
      (node (ref "C4") (pin "-") (pinfunction "-_-") (pintype "passive"))
      (node (ref "C5") (pin "-") (pinfunction "-_-") (pintype "passive"))
      (node (ref "C6") (pin "-") (pinfunction "-_-") (pintype "passive"))
      (node (ref "C7") (pin "-") (pinfunction "-_-") (pintype "passive"))
      (node (ref "C8") (pin "-") (pinfunction "-_-") (pintype "passive"))
      (node (ref "C9") (pin "1") (pinfunction "1_1") (pintype "passive"))
      (node (ref "CN5") (pin "2") (pinfunction "2_2") (pintype "bidirectional"))
      (node (ref "CN8") (pin "1") (pinfunction "1_1") (pintype "bidirectional"))
      (node (ref "CN8") (pin "2") (pinfunction "2_2") (pintype "bidirectional"))
      (node (ref "CN8") (pin "3") (pinfunction "3_3") (pintype "bidirectional"))
      (node (ref "CN8") (pin "4") (pinfunction "4_4") (pintype "bidirectional"))
      (node (ref "CN9") (pin "2") (pinfunction "2_2") (pintype "bidirectional"))
      (node (ref "EXP1") (pin "9") (pinfunction "9_9") (pintype "passive"))
      (node (ref "J1") (pin "1") (pinfunction "1_1") (pintype "passive"))
      (node (ref "JP1") (pin "2") (pinfunction "2_2") (pintype "passive"))
      (node (ref "JP1") (pin "4") (pinfunction "4_4") (pintype "passive"))
      (node (ref "JP1") (pin "6") (pinfunction "6_6") (pintype "passive"))
      (node (ref "JP1") (pin "8") (pinfunction "8_8") (pintype "passive"))
      (node (ref "JP10") (pin "2") (pinfunction "2_2") (pintype "passive"))
      (node (ref "JP11") (pin "2") (pinfunction "2_2") (pintype "passive"))
      (node (ref "JP12") (pin "2") (pinfunction "2_2") (pintype "passive"))
      (node (ref "JP13") (pin "2") (pinfunction "2_2") (pintype "passive"))
      (node (ref "JP14") (pin "2") (pinfunction "2_2") (pintype "passive"))
      (node (ref "JP15") (pin "1") (pinfunction "1_1") (pintype "passive"))
      (node (ref "JP15") (pin "3") (pinfunction "3_3") (pintype "passive"))
      (node (ref "JP15") (pin "5") (pinfunction "5_5") (pintype "passive"))
      (node (ref "JP15") (pin "7") (pinfunction "7_7") (pintype "passive"))
      (node (ref "JP17") (pin "1") (pinfunction "1_1") (pintype "passive"))
      (node (ref "JP2") (pin "1") (pinfunction "1_1") (pintype "passive"))
      (node (ref "JP3") (pin "1") (pinfunction "1_1") (pintype "passive"))
      (node (ref "JP3") (pin "3") (pinfunction "3_3") (pintype "passive"))
      (node (ref "JP3") (pin "5") (pinfunction "5_5") (pintype "passive"))
      (node (ref "JP3") (pin "7") (pinfunction "7_7") (pintype "passive"))
      (node (ref "JP5") (pin "3") (pinfunction "3_3") (pintype "passive"))
      (node (ref "JP5") (pin "4") (pinfunction "4_4") (pintype "passive"))
      (node (ref "JP6") (pin "2") (pinfunction "2_2") (pintype "passive"))
      (node (ref "JP7") (pin "2") (pinfunction "2_2") (pintype "passive"))
      (node (ref "JP8") (pin "2") (pinfunction "2_2") (pintype "passive"))
      (node (ref "JP9") (pin "2") (pinfunction "2_2") (pintype "passive"))
      (node (ref "LED5") (pin "C") (pinfunction "C_C") (pintype "passive"))
      (node (ref "Q1") (pin "1") (pinfunction "1_1") (pintype "bidirectional"))
      (node (ref "Q1") (pin "2") (pinfunction "2_2") (pintype "bidirectional"))
      (node (ref "Q1") (pin "3") (pinfunction "3_3") (pintype "bidirectional"))
      (node (ref "Q2") (pin "1") (pinfunction "1_1") (pintype "bidirectional"))
      (node (ref "Q2") (pin "2") (pinfunction "2_2") (pintype "bidirectional"))
      (node (ref "Q2") (pin "3") (pinfunction "3_3") (pintype "bidirectional"))
      (node (ref "Q3") (pin "1") (pinfunction "1_1") (pintype "bidirectional"))
      (node (ref "Q3") (pin "2") (pinfunction "2_2") (pintype "bidirectional"))
      (node (ref "Q3") (pin "3") (pinfunction "3_3") (pintype "bidirectional"))
      (node (ref "Q4") (pin "1") (pinfunction "1_1") (pintype "bidirectional"))
      (node (ref "Q4") (pin "2") (pinfunction "2_2") (pintype "bidirectional"))
      (node (ref "Q4") (pin "3") (pinfunction "3_3") (pintype "bidirectional"))
      (node (ref "R10") (pin "1") (pinfunction "1_1") (pintype "passive"))
      (node (ref "R19") (pin "1") (pinfunction "1_1") (pintype "passive"))
      (node (ref "R20") (pin "1") (pinfunction "1_1") (pintype "passive"))
      (node (ref "R21") (pin "1") (pinfunction "1_1") (pintype "passive"))
      (node (ref "R22") (pin "1") (pinfunction "1_1") (pintype "passive"))
      (node (ref "R5") (pin "1") (pinfunction "1_1") (pintype "passive"))
      (node (ref "R6") (pin "1") (pinfunction "1_1") (pintype "passive"))
      (node (ref "R7") (pin "1") (pinfunction "1_1") (pintype "passive"))
      (node (ref "R8") (pin "1") (pinfunction "1_1") (pintype "passive"))
      (node (ref "U$1") (pin "GND") (pinfunction "GND_GND") (pintype "power_in"))
      (node (ref "U$1") (pin "GND@0") (pinfunction "GND_GND@0") (pintype "power_in"))
      (node (ref "U$2") (pin "GND") (pinfunction "GND_GND") (pintype "power_in"))
      (node (ref "U$2") (pin "GND@0") (pinfunction "GND_GND@0") (pintype "power_in"))
      (node (ref "U$4") (pin "GND") (pinfunction "GND_GND") (pintype "power_in"))
      (node (ref "U$4") (pin "GND@0") (pinfunction "GND_GND@0") (pintype "power_in"))
      (node (ref "U$5") (pin "GND") (pinfunction "GND_GND") (pintype "power_in"))
      (node (ref "U$5") (pin "GND@0") (pinfunction "GND_GND@0") (pintype "power_in"))
      (node (ref "U$9") (pin "2") (pinfunction "2_2") (pintype "passive"))
    )
    (net (code "51") (name "Net-(CN1-Pad1)") (class "Default")
      (node (ref "CN1") (pin "1") (pinfunction "1_1") (pintype "bidirectional"))
      (node (ref "CN7") (pin "1") (pinfunction "1_1") (pintype "bidirectional"))
      (node (ref "U$1") (pin "2B") (pinfunction "2B_2B") (pintype "output"))
    )
    (net (code "52") (name "Net-(CN1-Pad2)") (class "Default")
      (node (ref "CN1") (pin "2") (pinfunction "2_2") (pintype "bidirectional"))
      (node (ref "CN7") (pin "2") (pinfunction "2_2") (pintype "bidirectional"))
      (node (ref "U$1") (pin "2A") (pinfunction "2A_2A") (pintype "output"))
    )
    (net (code "53") (name "Net-(CN1-Pad3)") (class "Default")
      (node (ref "CN1") (pin "3") (pinfunction "3_3") (pintype "bidirectional"))
      (node (ref "CN7") (pin "3") (pinfunction "3_3") (pintype "bidirectional"))
      (node (ref "U$1") (pin "1A") (pinfunction "1A_1A") (pintype "output"))
    )
    (net (code "54") (name "Net-(CN1-Pad4)") (class "Default")
      (node (ref "CN1") (pin "4") (pinfunction "4_4") (pintype "bidirectional"))
      (node (ref "CN7") (pin "4") (pinfunction "4_4") (pintype "bidirectional"))
      (node (ref "U$1") (pin "1B") (pinfunction "1B_1B") (pintype "output"))
    )
    (net (code "55") (name "Net-(CN2-Pad1)") (class "Default")
      (node (ref "CN2") (pin "1") (pinfunction "1_1") (pintype "bidirectional"))
      (node (ref "U$2") (pin "2B") (pinfunction "2B_2B") (pintype "output"))
    )
    (net (code "56") (name "Net-(CN2-Pad2)") (class "Default")
      (node (ref "CN2") (pin "2") (pinfunction "2_2") (pintype "bidirectional"))
      (node (ref "U$2") (pin "2A") (pinfunction "2A_2A") (pintype "output"))
    )
    (net (code "57") (name "Net-(CN2-Pad3)") (class "Default")
      (node (ref "CN2") (pin "3") (pinfunction "3_3") (pintype "bidirectional"))
      (node (ref "U$2") (pin "1A") (pinfunction "1A_1A") (pintype "output"))
    )
    (net (code "58") (name "Net-(CN2-Pad4)") (class "Default")
      (node (ref "CN2") (pin "4") (pinfunction "4_4") (pintype "bidirectional"))
      (node (ref "U$2") (pin "1B") (pinfunction "1B_1B") (pintype "output"))
    )
    (net (code "59") (name "Net-(CN3-Pad1)") (class "Default")
      (node (ref "CN3") (pin "1") (pinfunction "1_1") (pintype "bidirectional"))
      (node (ref "CN6") (pin "1") (pinfunction "1_1") (pintype "bidirectional"))
      (node (ref "U$4") (pin "2B") (pinfunction "2B_2B") (pintype "output"))
    )
    (net (code "60") (name "Net-(CN3-Pad2)") (class "Default")
      (node (ref "CN3") (pin "2") (pinfunction "2_2") (pintype "bidirectional"))
      (node (ref "CN6") (pin "2") (pinfunction "2_2") (pintype "bidirectional"))
      (node (ref "U$4") (pin "2A") (pinfunction "2A_2A") (pintype "output"))
    )
    (net (code "61") (name "Net-(CN3-Pad3)") (class "Default")
      (node (ref "CN3") (pin "3") (pinfunction "3_3") (pintype "bidirectional"))
      (node (ref "CN6") (pin "3") (pinfunction "3_3") (pintype "bidirectional"))
      (node (ref "U$4") (pin "1A") (pinfunction "1A_1A") (pintype "output"))
    )
    (net (code "62") (name "Net-(CN3-Pad4)") (class "Default")
      (node (ref "CN3") (pin "4") (pinfunction "4_4") (pintype "bidirectional"))
      (node (ref "CN6") (pin "4") (pinfunction "4_4") (pintype "bidirectional"))
      (node (ref "U$4") (pin "1B") (pinfunction "1B_1B") (pintype "output"))
    )
    (net (code "63") (name "Net-(CN4-Pad1)") (class "Default")
      (node (ref "CN4") (pin "1") (pinfunction "1_1") (pintype "bidirectional"))
      (node (ref "U$5") (pin "2B") (pinfunction "2B_2B") (pintype "output"))
    )
    (net (code "64") (name "Net-(CN4-Pad2)") (class "Default")
      (node (ref "CN4") (pin "2") (pinfunction "2_2") (pintype "bidirectional"))
      (node (ref "U$5") (pin "2A") (pinfunction "2A_2A") (pintype "output"))
    )
    (net (code "65") (name "Net-(CN4-Pad3)") (class "Default")
      (node (ref "CN4") (pin "3") (pinfunction "3_3") (pintype "bidirectional"))
      (node (ref "U$5") (pin "1A") (pinfunction "1A_1A") (pintype "output"))
    )
    (net (code "66") (name "Net-(CN4-Pad4)") (class "Default")
      (node (ref "CN4") (pin "4") (pinfunction "4_4") (pintype "bidirectional"))
      (node (ref "U$5") (pin "1B") (pinfunction "1B_1B") (pintype "output"))
    )
    (net (code "67") (name "Net-(F1-Pad1)") (class "Default")
      (node (ref "F1") (pin "1") (pinfunction "1_1") (pintype "passive"))
      (node (ref "J1") (pin "2") (pinfunction "2_2") (pintype "passive"))
    )
    (net (code "68") (name "Net-(J2-Pad1)") (class "Default")
      (node (ref "J2") (pin "1") (pinfunction "1_1") (pintype "passive"))
      (node (ref "LED1") (pin "C") (pinfunction "C_C") (pintype "passive"))
      (node (ref "Q1") (pin "5") (pinfunction "5_5") (pintype "bidirectional"))
    )
    (net (code "69") (name "Net-(J3-Pad1)") (class "Default")
      (node (ref "J3") (pin "1") (pinfunction "1_1") (pintype "passive"))
      (node (ref "LED2") (pin "C") (pinfunction "C_C") (pintype "passive"))
      (node (ref "Q2") (pin "5") (pinfunction "5_5") (pintype "bidirectional"))
    )
    (net (code "70") (name "Net-(J4-Pad1)") (class "Default")
      (node (ref "J4") (pin "1") (pinfunction "1_1") (pintype "passive"))
      (node (ref "LED3") (pin "C") (pinfunction "C_C") (pintype "passive"))
      (node (ref "Q3") (pin "5") (pinfunction "5_5") (pintype "bidirectional"))
    )
    (net (code "71") (name "Net-(J5-Pad1)") (class "Default")
      (node (ref "J5") (pin "1") (pinfunction "1_1") (pintype "passive"))
      (node (ref "LED4") (pin "C") (pinfunction "C_C") (pintype "passive"))
      (node (ref "Q4") (pin "5") (pinfunction "5_5") (pintype "bidirectional"))
    )
    (net (code "72") (name "Net-(LED1-PadA)") (class "Default")
      (node (ref "LED1") (pin "A") (pinfunction "A_A") (pintype "passive"))
      (node (ref "R11") (pin "2") (pinfunction "2_2") (pintype "passive"))
    )
    (net (code "73") (name "Net-(LED2-PadA)") (class "Default")
      (node (ref "LED2") (pin "A") (pinfunction "A_A") (pintype "passive"))
      (node (ref "R12") (pin "2") (pinfunction "2_2") (pintype "passive"))
    )
    (net (code "74") (name "Net-(LED3-PadA)") (class "Default")
      (node (ref "LED3") (pin "A") (pinfunction "A_A") (pintype "passive"))
      (node (ref "R13") (pin "2") (pinfunction "2_2") (pintype "passive"))
    )
    (net (code "75") (name "Net-(LED4-PadA)") (class "Default")
      (node (ref "LED4") (pin "A") (pinfunction "A_A") (pintype "passive"))
      (node (ref "R14") (pin "2") (pinfunction "2_2") (pintype "passive"))
    )
    (net (code "76") (name "Net-(LED5-PadA)") (class "Default")
      (node (ref "LED5") (pin "A") (pinfunction "A_A") (pintype "passive"))
      (node (ref "R27") (pin "2") (pinfunction "2_2") (pintype "passive"))
    )
    (net (code "77") (name "Net-(Q1-Pad4)") (class "Default")
      (node (ref "Q1") (pin "4") (pinfunction "4_4") (pintype "bidirectional"))
      (node (ref "R15") (pin "1") (pinfunction "1_1") (pintype "passive"))
    )
    (net (code "78") (name "Net-(Q2-Pad4)") (class "Default")
      (node (ref "Q2") (pin "4") (pinfunction "4_4") (pintype "bidirectional"))
      (node (ref "R16") (pin "1") (pinfunction "1_1") (pintype "passive"))
    )
    (net (code "79") (name "Net-(Q3-Pad4)") (class "Default")
      (node (ref "Q3") (pin "4") (pinfunction "4_4") (pintype "bidirectional"))
      (node (ref "R17") (pin "1") (pinfunction "1_1") (pintype "passive"))
    )
    (net (code "80") (name "Net-(Q4-Pad4)") (class "Default")
      (node (ref "Q4") (pin "4") (pinfunction "4_4") (pintype "bidirectional"))
      (node (ref "R18") (pin "1") (pinfunction "1_1") (pintype "passive"))
    )
    (net (code "81") (name "Net-(R5-Pad2)") (class "Default")
      (node (ref "R5") (pin "2") (pinfunction "2_2") (pintype "passive"))
      (node (ref "SV1") (pin "1") (pinfunction "1_1") (pintype "passive"))
      (node (ref "U$1") (pin "MS1") (pinfunction "MS1_MS1") (pintype "input"))
    )
    (net (code "82") (name "Net-(R6-Pad2)") (class "Default")
      (node (ref "R6") (pin "2") (pinfunction "2_2") (pintype "passive"))
      (node (ref "SV2") (pin "1") (pinfunction "1_1") (pintype "passive"))
      (node (ref "U$2") (pin "MS1") (pinfunction "MS1_MS1") (pintype "input"))
    )
    (net (code "83") (name "Net-(R7-Pad2)") (class "Default")
      (node (ref "R7") (pin "2") (pinfunction "2_2") (pintype "passive"))
      (node (ref "SV3") (pin "1") (pinfunction "1_1") (pintype "passive"))
      (node (ref "U$4") (pin "MS1") (pinfunction "MS1_MS1") (pintype "input"))
    )
    (net (code "84") (name "Net-(R8-Pad2)") (class "Default")
      (node (ref "R8") (pin "2") (pinfunction "2_2") (pintype "passive"))
      (node (ref "SV4") (pin "1") (pinfunction "1_1") (pintype "passive"))
      (node (ref "U$5") (pin "MS1") (pinfunction "MS1_MS1") (pintype "input"))
    )
    (net (code "85") (name "Net-(SV1-Pad3)") (class "Default")
      (node (ref "SV1") (pin "3") (pinfunction "3_3") (pintype "passive"))
      (node (ref "U$1") (pin "MS2") (pinfunction "MS2_MS2") (pintype "input"))
    )
    (net (code "86") (name "Net-(SV1-Pad5)") (class "Default")
      (node (ref "SV1") (pin "5") (pinfunction "5_5") (pintype "passive"))
      (node (ref "U$1") (pin "MS3") (pinfunction "MS3_MS3") (pintype "input"))
    )
    (net (code "87") (name "Net-(SV2-Pad3)") (class "Default")
      (node (ref "SV2") (pin "3") (pinfunction "3_3") (pintype "passive"))
      (node (ref "U$2") (pin "MS2") (pinfunction "MS2_MS2") (pintype "input"))
    )
    (net (code "88") (name "Net-(SV2-Pad5)") (class "Default")
      (node (ref "SV2") (pin "5") (pinfunction "5_5") (pintype "passive"))
      (node (ref "U$2") (pin "MS3") (pinfunction "MS3_MS3") (pintype "input"))
    )
    (net (code "89") (name "Net-(SV3-Pad3)") (class "Default")
      (node (ref "SV3") (pin "3") (pinfunction "3_3") (pintype "passive"))
      (node (ref "U$4") (pin "MS2") (pinfunction "MS2_MS2") (pintype "input"))
    )
    (net (code "90") (name "Net-(SV3-Pad5)") (class "Default")
      (node (ref "SV3") (pin "5") (pinfunction "5_5") (pintype "passive"))
      (node (ref "U$4") (pin "MS3") (pinfunction "MS3_MS3") (pintype "input"))
    )
    (net (code "91") (name "Net-(SV4-Pad3)") (class "Default")
      (node (ref "SV4") (pin "3") (pinfunction "3_3") (pintype "passive"))
      (node (ref "U$5") (pin "MS2") (pinfunction "MS2_MS2") (pintype "input"))
    )
    (net (code "92") (name "Net-(SV4-Pad5)") (class "Default")
      (node (ref "SV4") (pin "5") (pinfunction "5_5") (pintype "passive"))
      (node (ref "U$5") (pin "MS3") (pinfunction "MS3_MS3") (pintype "input"))
    )
    (net (code "93") (name "Net-(U$1-SLEEP)") (class "Default")
      (node (ref "U$1") (pin "RST") (pinfunction "RST_RST") (pintype "input"))
      (node (ref "U$1") (pin "SLP") (pinfunction "SLEEP_SLP") (pintype "input"))
    )
    (net (code "94") (name "Net-(U$2-SLEEP)") (class "Default")
      (node (ref "U$2") (pin "RST") (pinfunction "RST_RST") (pintype "input"))
      (node (ref "U$2") (pin "SLP") (pinfunction "SLEEP_SLP") (pintype "input"))
    )
    (net (code "95") (name "Net-(U$4-SLEEP)") (class "Default")
      (node (ref "U$4") (pin "RST") (pinfunction "RST_RST") (pintype "input"))
      (node (ref "U$4") (pin "SLP") (pinfunction "SLEEP_SLP") (pintype "input"))
    )
    (net (code "96") (name "Net-(U$5-SLEEP)") (class "Default")
      (node (ref "U$5") (pin "RST") (pinfunction "RST_RST") (pintype "input"))
      (node (ref "U$5") (pin "SLP") (pinfunction "SLEEP_SLP") (pintype "input"))
    )
    (net (code "97") (name "unconnected-(EXP2-Pad9)") (class "Default")
      (node (ref "EXP2") (pin "9") (pinfunction "9_9") (pintype "passive"))
    )
    (net (code "98") (name "unconnected-(EXP2-Pad10)") (class "Default")
      (node (ref "EXP2") (pin "10") (pinfunction "10_10") (pintype "passive"))
    )
    (net (code "99") (name "unconnected-(U$3-Pad7)") (class "Default")
      (node (ref "U$3") (pin "7") (pinfunction "7_7") (pintype "passive"))
    )
    (net (code "100") (name "unconnected-(U$3-Pad8)") (class "Default")
      (node (ref "U$3") (pin "8") (pinfunction "8_8") (pintype "passive"))
    )
    (net (code "101") (name "unconnected-(U$10-Pad1)") (class "Default")
      (node (ref "U$10") (pin "1") (pinfunction "1_1") (pintype "passive"))
    )
    (net (code "102") (name "unconnected-(U$10-Pad2)") (class "Default")
      (node (ref "U$10") (pin "2") (pinfunction "2_2") (pintype "passive"))
    )
  )
)
